# BUS.net
KiCad netlist of a schematic drawn in EAGLE
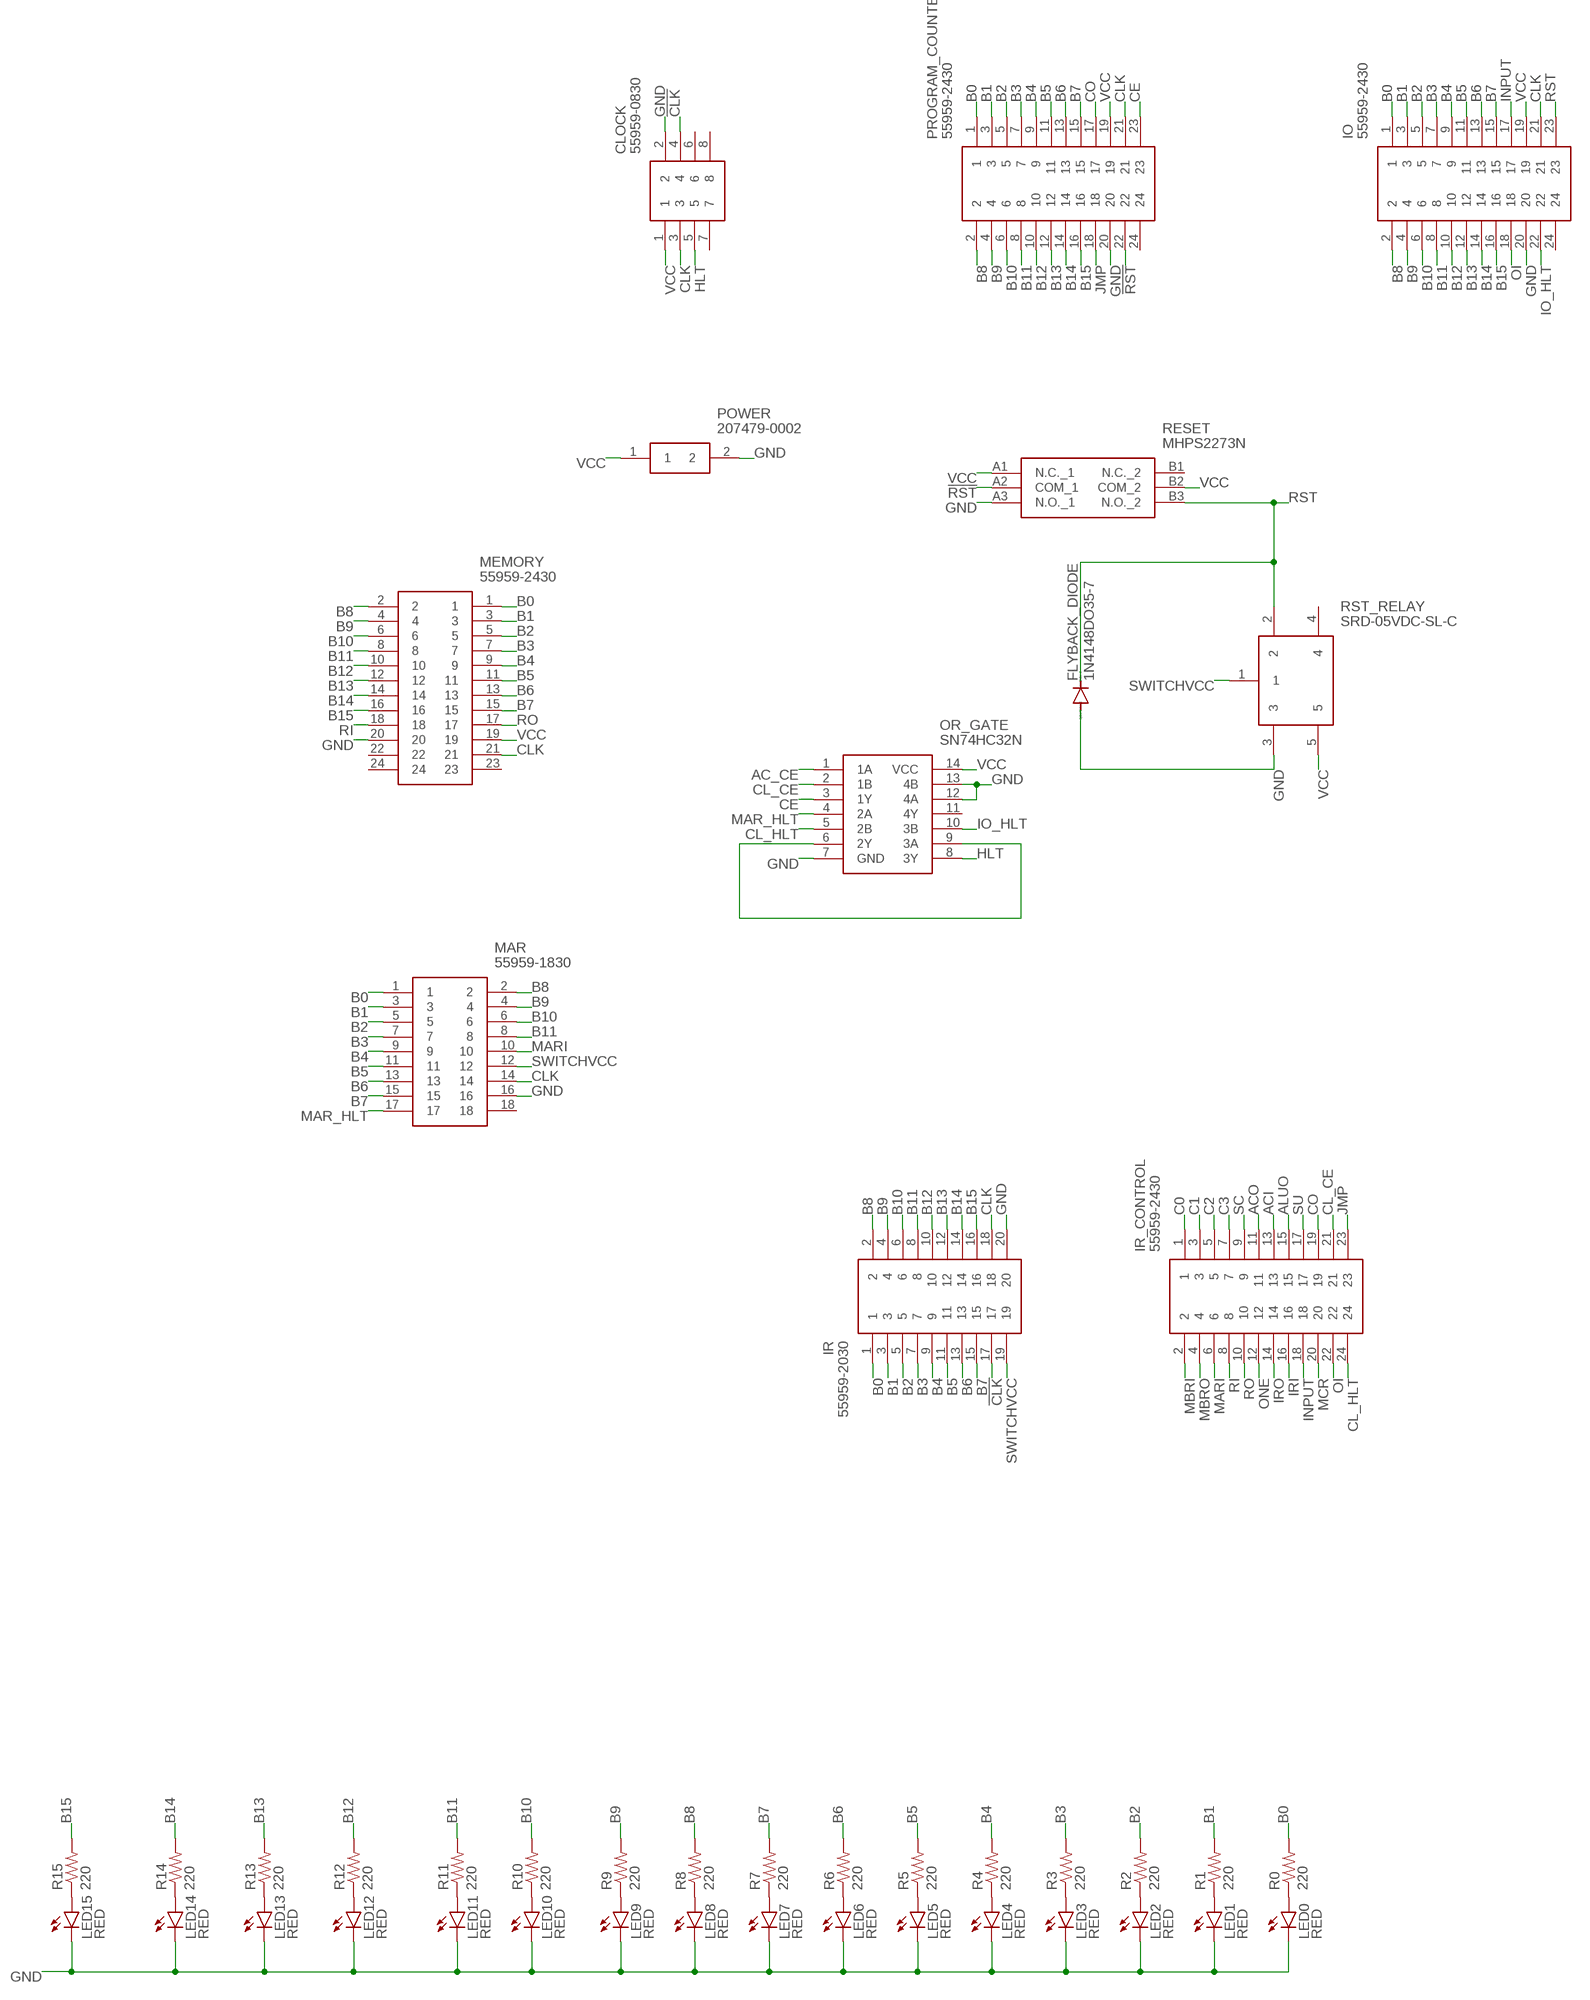
[diagram p0: schematic, sheet 1, part 1 of 2]
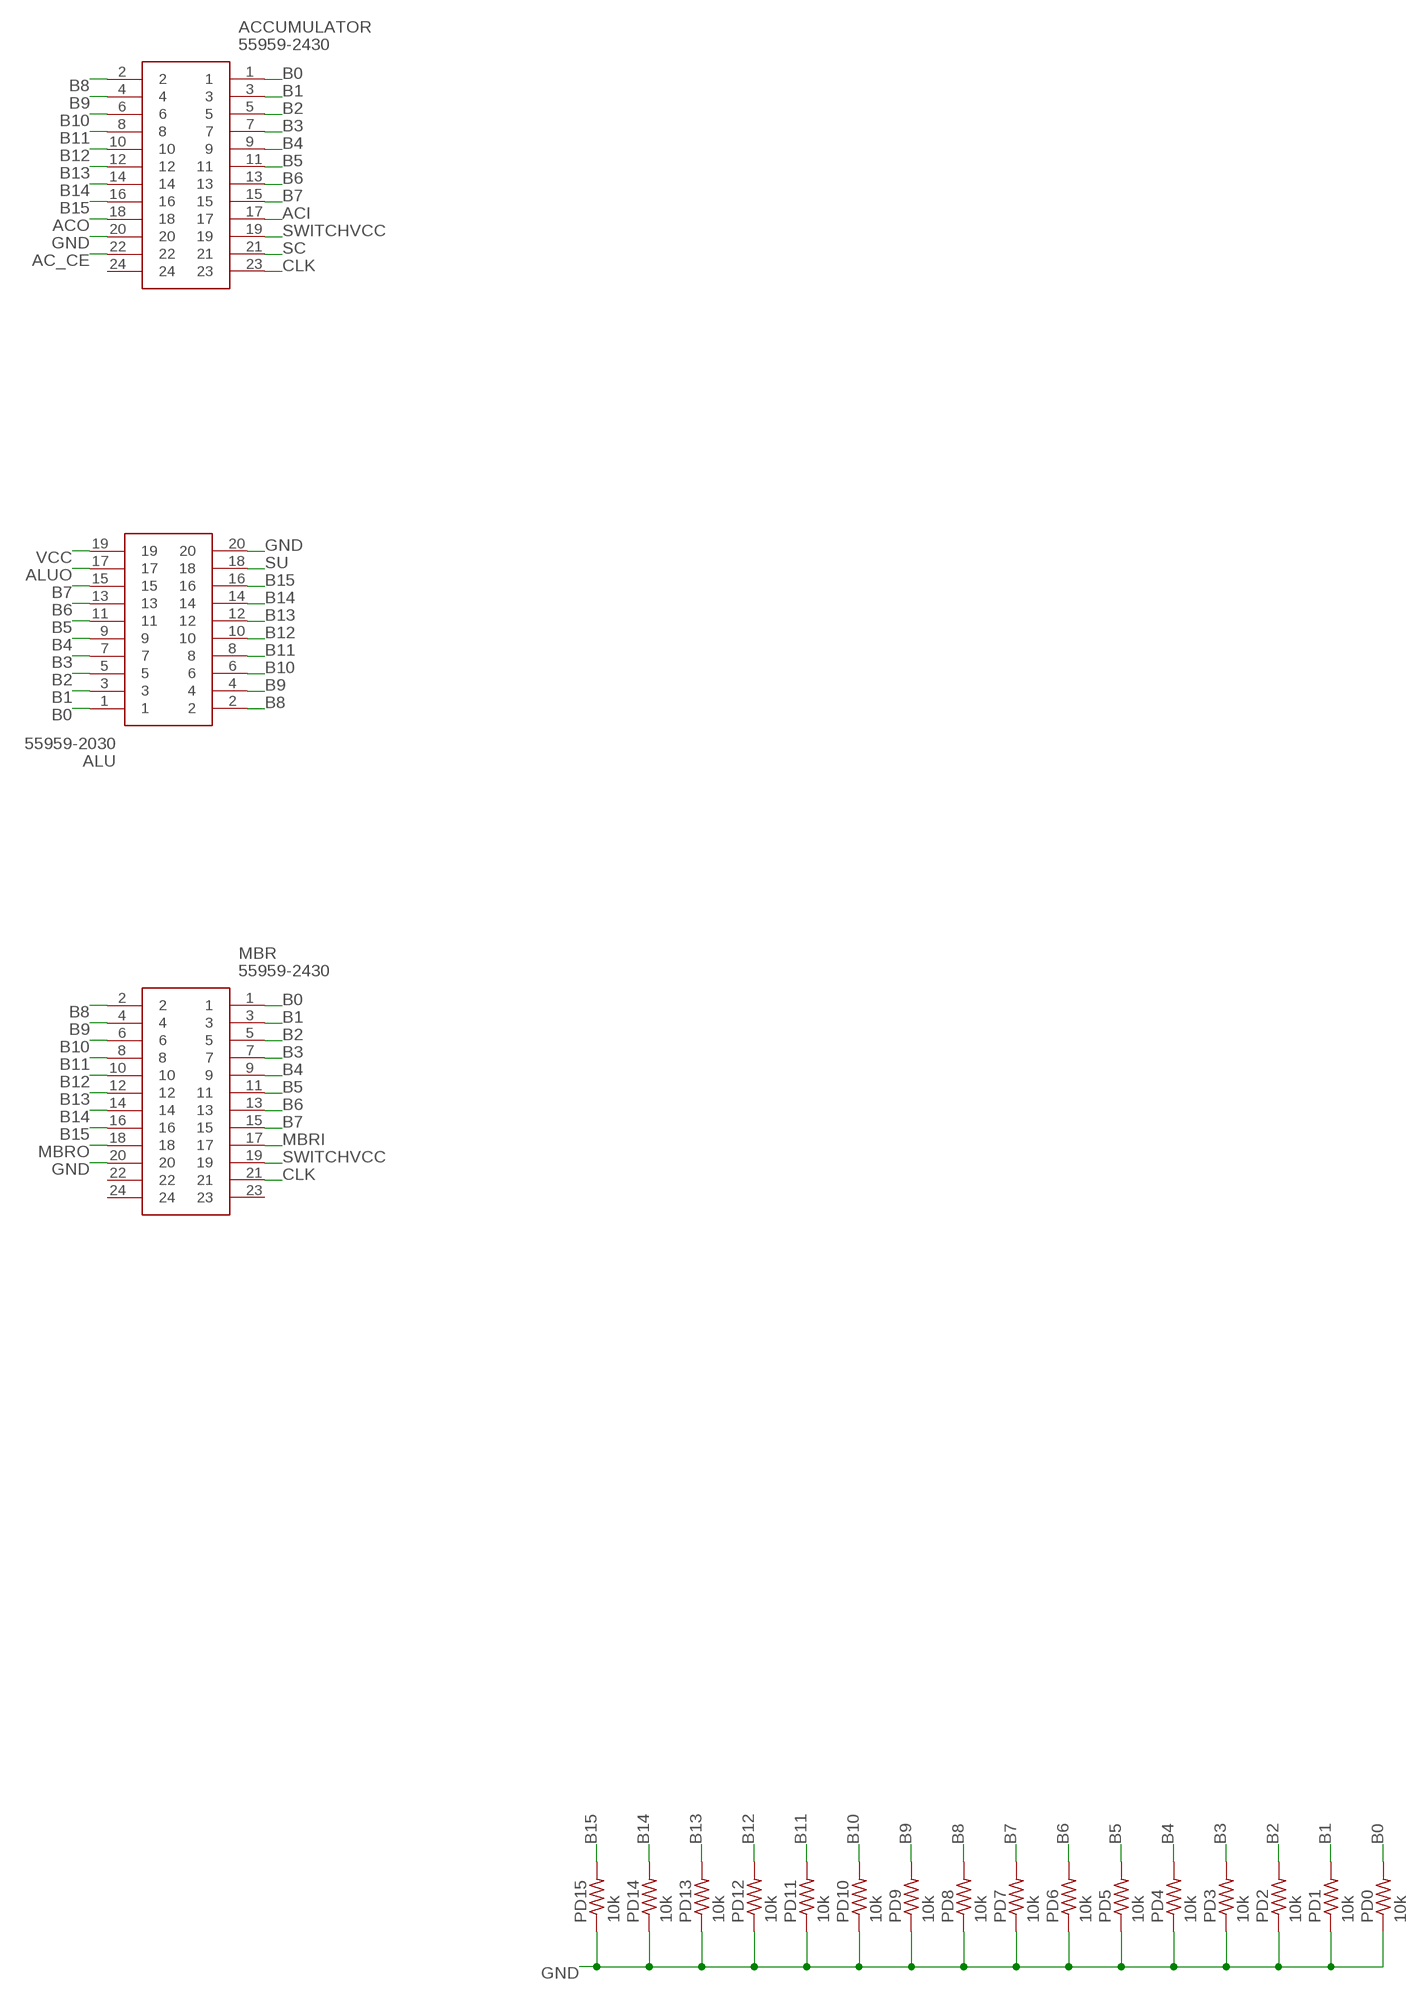
[diagram p1: schematic, sheet 1, part 2 of 2]

(export (version "E")
  (design (tool "Eeschema 10.0.6"))
  (components
    (comp (ref "ACCUMULATOR")
      (value "55959-2430")
      (footprint "eagle-import:559592430")
      (fields (field (name "MOUSER_PART_NUMBER") "538-55959-2430"))
      (libsource (lib "eagle-import") (part "55959-2430"))
    )
    (comp (ref "ALU")
      (value "55959-2030")
      (footprint "eagle-import:55959-2030_1")
      (fields (field (name "MOUSER_PART_NUMBER") "538-55959-2030"))
      (libsource (lib "eagle-import") (part "55959-2030"))
    )
    (comp (ref "CLOCK")
      (value "55959-0830")
      (footprint "eagle-import:SHDR8W65P250X200_2X4_1140X1400")
      (fields (field (name "MOUSER_PART_NUMBER") "538-55959-0830"))
      (libsource (lib "eagle-import") (part "55959-0830"))
    )
    (comp (ref "FLYBACK_DIODE")
      (value "1N4148DO35-7")
      (footprint "eagle-import:DO35-7")
      (libsource (lib "eagle-import") (part "1N4148DO35-7"))
    )
    (comp (ref "IO")
      (value "55959-2430")
      (footprint "eagle-import:559592430")
      (fields (field (name "MOUSER_PART_NUMBER") "538-55959-2430"))
      (libsource (lib "eagle-import") (part "55959-2430"))
    )
    (comp (ref "IR")
      (value "55959-2030")
      (footprint "eagle-import:55959-2030_1")
      (fields (field (name "MOUSER_PART_NUMBER") "538-55959-2030"))
      (libsource (lib "eagle-import") (part "55959-2030"))
    )
    (comp (ref "IR_CONTROL")
      (value "55959-2430")
      (footprint "eagle-import:559592430")
      (fields (field (name "MOUSER_PART_NUMBER") "538-55959-2430"))
      (libsource (lib "eagle-import") (part "55959-2430"))
    )
    (comp (ref "LED0")
      (value "RED")
      (footprint "eagle-import:LED3MM")
      (libsource (lib "eagle-import") (part "LED3MM"))
    )
    (comp (ref "LED1")
      (value "RED")
      (footprint "eagle-import:LED3MM")
      (libsource (lib "eagle-import") (part "LED3MM"))
    )
    (comp (ref "LED2")
      (value "RED")
      (footprint "eagle-import:LED3MM")
      (libsource (lib "eagle-import") (part "LED3MM"))
    )
    (comp (ref "LED3")
      (value "RED")
      (footprint "eagle-import:LED3MM")
      (libsource (lib "eagle-import") (part "LED3MM"))
    )
    (comp (ref "LED4")
      (value "RED")
      (footprint "eagle-import:LED3MM")
      (libsource (lib "eagle-import") (part "LED3MM"))
    )
    (comp (ref "LED5")
      (value "RED")
      (footprint "eagle-import:LED3MM")
      (libsource (lib "eagle-import") (part "LED3MM"))
    )
    (comp (ref "LED6")
      (value "RED")
      (footprint "eagle-import:LED3MM")
      (libsource (lib "eagle-import") (part "LED3MM"))
    )
    (comp (ref "LED7")
      (value "RED")
      (footprint "eagle-import:LED3MM")
      (libsource (lib "eagle-import") (part "LED3MM"))
    )
    (comp (ref "LED8")
      (value "RED")
      (footprint "eagle-import:LED3MM")
      (libsource (lib "eagle-import") (part "LED3MM"))
    )
    (comp (ref "LED9")
      (value "RED")
      (footprint "eagle-import:LED3MM")
      (libsource (lib "eagle-import") (part "LED3MM"))
    )
    (comp (ref "LED10")
      (value "RED")
      (footprint "eagle-import:LED3MM")
      (libsource (lib "eagle-import") (part "LED3MM"))
    )
    (comp (ref "LED11")
      (value "RED")
      (footprint "eagle-import:LED3MM")
      (libsource (lib "eagle-import") (part "LED3MM"))
    )
    (comp (ref "LED12")
      (value "RED")
      (footprint "eagle-import:LED3MM")
      (libsource (lib "eagle-import") (part "LED3MM"))
    )
    (comp (ref "LED13")
      (value "RED")
      (footprint "eagle-import:LED3MM")
      (libsource (lib "eagle-import") (part "LED3MM"))
    )
    (comp (ref "LED14")
      (value "RED")
      (footprint "eagle-import:LED3MM")
      (libsource (lib "eagle-import") (part "LED3MM"))
    )
    (comp (ref "LED15")
      (value "RED")
      (footprint "eagle-import:LED3MM")
      (libsource (lib "eagle-import") (part "LED3MM"))
    )
    (comp (ref "MAR")
      (value "55959-1830")
      (footprint "eagle-import:SHDR18W65P250X200_2X9_2140X140")
      (fields (field (name "MOUSER_PART_NUMBER") "538-55959-1830"))
      (libsource (lib "eagle-import") (part "55959-1830"))
    )
    (comp (ref "MBR")
      (value "55959-2430")
      (footprint "eagle-import:559592430")
      (fields (field (name "MOUSER_PART_NUMBER") "538-55959-2430"))
      (libsource (lib "eagle-import") (part "55959-2430"))
    )
    (comp (ref "MEMORY")
      (value "55959-2430")
      (footprint "eagle-import:559592430")
      (fields (field (name "MOUSER_PART_NUMBER") "538-55959-2430"))
      (libsource (lib "eagle-import") (part "55959-2430"))
    )
    (comp (ref "OR_GATE")
      (value "SN74HC32N")
      (footprint "eagle-import:DIP794W53P254L1930H508Q14N")
      (fields (field (name "MOUSER_PART_NUMBER") "595-SN74HC32N"))
      (libsource (lib "eagle-import") (part "SN74HC32N"))
    )
    (comp (ref "PD0")
      (value "10k")
      (footprint "eagle-import:0204_7")
      (libsource (lib "eagle-import") (part "R-US_0204/7"))
    )
    (comp (ref "PD1")
      (value "10k")
      (footprint "eagle-import:0204_7")
      (libsource (lib "eagle-import") (part "R-US_0204/7"))
    )
    (comp (ref "PD2")
      (value "10k")
      (footprint "eagle-import:0204_7")
      (libsource (lib "eagle-import") (part "R-US_0204/7"))
    )
    (comp (ref "PD3")
      (value "10k")
      (footprint "eagle-import:0204_7")
      (libsource (lib "eagle-import") (part "R-US_0204/7"))
    )
    (comp (ref "PD4")
      (value "10k")
      (footprint "eagle-import:0204_7")
      (libsource (lib "eagle-import") (part "R-US_0204/7"))
    )
    (comp (ref "PD5")
      (value "10k")
      (footprint "eagle-import:0204_7")
      (libsource (lib "eagle-import") (part "R-US_0204/7"))
    )
    (comp (ref "PD6")
      (value "10k")
      (footprint "eagle-import:0204_7")
      (libsource (lib "eagle-import") (part "R-US_0204/7"))
    )
    (comp (ref "PD7")
      (value "10k")
      (footprint "eagle-import:0204_7")
      (libsource (lib "eagle-import") (part "R-US_0204/7"))
    )
    (comp (ref "PD8")
      (value "10k")
      (footprint "eagle-import:0204_7")
      (libsource (lib "eagle-import") (part "R-US_0204/7"))
    )
    (comp (ref "PD9")
      (value "10k")
      (footprint "eagle-import:0204_7")
      (libsource (lib "eagle-import") (part "R-US_0204/7"))
    )
    (comp (ref "PD10")
      (value "10k")
      (footprint "eagle-import:0204_7")
      (libsource (lib "eagle-import") (part "R-US_0204/7"))
    )
    (comp (ref "PD11")
      (value "10k")
      (footprint "eagle-import:0204_7")
      (libsource (lib "eagle-import") (part "R-US_0204/7"))
    )
    (comp (ref "PD12")
      (value "10k")
      (footprint "eagle-import:0204_7")
      (libsource (lib "eagle-import") (part "R-US_0204/7"))
    )
    (comp (ref "PD13")
      (value "10k")
      (footprint "eagle-import:0204_7")
      (libsource (lib "eagle-import") (part "R-US_0204/7"))
    )
    (comp (ref "PD14")
      (value "10k")
      (footprint "eagle-import:0204_7")
      (libsource (lib "eagle-import") (part "R-US_0204/7"))
    )
    (comp (ref "PD15")
      (value "10k")
      (footprint "eagle-import:0204_7")
      (libsource (lib "eagle-import") (part "R-US_0204/7"))
    )
    (comp (ref "POWER")
      (value "207479-0002")
      (footprint "eagle-import:2074790002")
      (fields (field (name "MOUSER_PART_NUMBER") "538-207479-0002"))
      (libsource (lib "eagle-import") (part "207479-0002"))
    )
    (comp (ref "PROGRAM_COUNTER")
      (value "55959-2430")
      (footprint "eagle-import:559592430")
      (fields (field (name "MOUSER_PART_NUMBER") "538-55959-2430"))
      (libsource (lib "eagle-import") (part "55959-2430"))
    )
    (comp (ref "R0")
      (value "220")
      (footprint "eagle-import:0204_7")
      (libsource (lib "eagle-import") (part "R-US_0204/7"))
    )
    (comp (ref "R1")
      (value "220")
      (footprint "eagle-import:0204_7")
      (libsource (lib "eagle-import") (part "R-US_0204/7"))
    )
    (comp (ref "R2")
      (value "220")
      (footprint "eagle-import:0204_7")
      (libsource (lib "eagle-import") (part "R-US_0204/7"))
    )
    (comp (ref "R3")
      (value "220")
      (footprint "eagle-import:0204_7")
      (libsource (lib "eagle-import") (part "R-US_0204/7"))
    )
    (comp (ref "R4")
      (value "220")
      (footprint "eagle-import:0204_7")
      (libsource (lib "eagle-import") (part "R-US_0204/7"))
    )
    (comp (ref "R5")
      (value "220")
      (footprint "eagle-import:0204_7")
      (libsource (lib "eagle-import") (part "R-US_0204/7"))
    )
    (comp (ref "R6")
      (value "220")
      (footprint "eagle-import:0204_7")
      (libsource (lib "eagle-import") (part "R-US_0204/7"))
    )
    (comp (ref "R7")
      (value "220")
      (footprint "eagle-import:0204_7")
      (libsource (lib "eagle-import") (part "R-US_0204/7"))
    )
    (comp (ref "R8")
      (value "220")
      (footprint "eagle-import:0204_7")
      (libsource (lib "eagle-import") (part "R-US_0204/7"))
    )
    (comp (ref "R9")
      (value "220")
      (footprint "eagle-import:0204_7")
      (libsource (lib "eagle-import") (part "R-US_0204/7"))
    )
    (comp (ref "R10")
      (value "220")
      (footprint "eagle-import:0204_7")
      (libsource (lib "eagle-import") (part "R-US_0204/7"))
    )
    (comp (ref "R11")
      (value "220")
      (footprint "eagle-import:0204_7")
      (libsource (lib "eagle-import") (part "R-US_0204/7"))
    )
    (comp (ref "R12")
      (value "220")
      (footprint "eagle-import:0204_7")
      (libsource (lib "eagle-import") (part "R-US_0204/7"))
    )
    (comp (ref "R13")
      (value "220")
      (footprint "eagle-import:0204_7")
      (libsource (lib "eagle-import") (part "R-US_0204/7"))
    )
    (comp (ref "R14")
      (value "220")
      (footprint "eagle-import:0204_7")
      (libsource (lib "eagle-import") (part "R-US_0204/7"))
    )
    (comp (ref "R15")
      (value "220")
      (footprint "eagle-import:0204_7")
      (libsource (lib "eagle-import") (part "R-US_0204/7"))
    )
    (comp (ref "RESET")
      (value "MHPS2273N")
      (footprint "eagle-import:MHPS2273N")
      (fields (field (name "MOUSER_PART_NUMBER") "642-MHPS2273N"))
      (libsource (lib "eagle-import") (part "MHPS2273N"))
    )
    (comp (ref "RST_RELAY")
      (value "SRD-05VDC-SL-C")
      (footprint "eagle-import:SRD")
      (libsource (lib "eagle-import") (part "SRD-05VDC-SL-C"))
    )
  )
  (nets
    (net (code "1") (name "/ACI") (class "Default")
      (node (ref "ACCUMULATOR") (pin "17") (pinfunction "17_17") (pintype "bidirectional"))
      (node (ref "IR_CONTROL") (pin "13") (pinfunction "13_13") (pintype "bidirectional"))
    )
    (net (code "2") (name "/ACO") (class "Default")
      (node (ref "ACCUMULATOR") (pin "18") (pinfunction "18_18") (pintype "bidirectional"))
      (node (ref "IR_CONTROL") (pin "11") (pinfunction "11_11") (pintype "bidirectional"))
    )
    (net (code "3") (name "/AC_CE") (class "Default")
      (node (ref "ACCUMULATOR") (pin "22") (pinfunction "22_22") (pintype "bidirectional"))
      (node (ref "OR_GATE") (pin "1") (pinfunction "1A_1") (pintype "bidirectional"))
    )
    (net (code "4") (name "/ALUO") (class "Default")
      (node (ref "ALU") (pin "17") (pinfunction "17_17") (pintype "bidirectional"))
      (node (ref "IR_CONTROL") (pin "15") (pinfunction "15_15") (pintype "bidirectional"))
    )
    (net (code "5") (name "/B0") (class "Default")
      (node (ref "ACCUMULATOR") (pin "1") (pinfunction "1_1") (pintype "bidirectional"))
      (node (ref "ALU") (pin "1") (pinfunction "1_1") (pintype "bidirectional"))
      (node (ref "IO") (pin "1") (pinfunction "1_1") (pintype "bidirectional"))
      (node (ref "IR") (pin "1") (pinfunction "1_1") (pintype "bidirectional"))
      (node (ref "MAR") (pin "1") (pinfunction "1_1") (pintype "bidirectional"))
      (node (ref "MBR") (pin "1") (pinfunction "1_1") (pintype "bidirectional"))
      (node (ref "MEMORY") (pin "1") (pinfunction "1_1") (pintype "bidirectional"))
      (node (ref "PD0") (pin "2") (pinfunction "2_2") (pintype "passive"))
      (node (ref "PROGRAM_COUNTER") (pin "1") (pinfunction "1_1") (pintype "bidirectional"))
      (node (ref "R0") (pin "2") (pinfunction "2_2") (pintype "passive"))
    )
    (net (code "6") (name "/B1") (class "Default")
      (node (ref "ACCUMULATOR") (pin "3") (pinfunction "3_3") (pintype "bidirectional"))
      (node (ref "ALU") (pin "3") (pinfunction "3_3") (pintype "bidirectional"))
      (node (ref "IO") (pin "3") (pinfunction "3_3") (pintype "bidirectional"))
      (node (ref "IR") (pin "3") (pinfunction "3_3") (pintype "bidirectional"))
      (node (ref "MAR") (pin "3") (pinfunction "3_3") (pintype "bidirectional"))
      (node (ref "MBR") (pin "3") (pinfunction "3_3") (pintype "bidirectional"))
      (node (ref "MEMORY") (pin "3") (pinfunction "3_3") (pintype "bidirectional"))
      (node (ref "PD1") (pin "2") (pinfunction "2_2") (pintype "passive"))
      (node (ref "PROGRAM_COUNTER") (pin "3") (pinfunction "3_3") (pintype "bidirectional"))
      (node (ref "R1") (pin "2") (pinfunction "2_2") (pintype "passive"))
    )
    (net (code "7") (name "/B2") (class "Default")
      (node (ref "ACCUMULATOR") (pin "5") (pinfunction "5_5") (pintype "bidirectional"))
      (node (ref "ALU") (pin "5") (pinfunction "5_5") (pintype "bidirectional"))
      (node (ref "IO") (pin "5") (pinfunction "5_5") (pintype "bidirectional"))
      (node (ref "IR") (pin "5") (pinfunction "5_5") (pintype "bidirectional"))
      (node (ref "MAR") (pin "5") (pinfunction "5_5") (pintype "bidirectional"))
      (node (ref "MBR") (pin "5") (pinfunction "5_5") (pintype "bidirectional"))
      (node (ref "MEMORY") (pin "5") (pinfunction "5_5") (pintype "bidirectional"))
      (node (ref "PD2") (pin "2") (pinfunction "2_2") (pintype "passive"))
      (node (ref "PROGRAM_COUNTER") (pin "5") (pinfunction "5_5") (pintype "bidirectional"))
      (node (ref "R2") (pin "2") (pinfunction "2_2") (pintype "passive"))
    )
    (net (code "8") (name "/B3") (class "Default")
      (node (ref "ACCUMULATOR") (pin "7") (pinfunction "7_7") (pintype "bidirectional"))
      (node (ref "ALU") (pin "7") (pinfunction "7_7") (pintype "bidirectional"))
      (node (ref "IO") (pin "7") (pinfunction "7_7") (pintype "bidirectional"))
      (node (ref "IR") (pin "7") (pinfunction "7_7") (pintype "bidirectional"))
      (node (ref "MAR") (pin "7") (pinfunction "7_7") (pintype "bidirectional"))
      (node (ref "MBR") (pin "7") (pinfunction "7_7") (pintype "bidirectional"))
      (node (ref "MEMORY") (pin "7") (pinfunction "7_7") (pintype "bidirectional"))
      (node (ref "PD3") (pin "2") (pinfunction "2_2") (pintype "passive"))
      (node (ref "PROGRAM_COUNTER") (pin "7") (pinfunction "7_7") (pintype "bidirectional"))
      (node (ref "R3") (pin "2") (pinfunction "2_2") (pintype "passive"))
    )
    (net (code "9") (name "/B4") (class "Default")
      (node (ref "ACCUMULATOR") (pin "9") (pinfunction "9_9") (pintype "bidirectional"))
      (node (ref "ALU") (pin "9") (pinfunction "9_9") (pintype "bidirectional"))
      (node (ref "IO") (pin "9") (pinfunction "9_9") (pintype "bidirectional"))
      (node (ref "IR") (pin "9") (pinfunction "9_9") (pintype "bidirectional"))
      (node (ref "MAR") (pin "9") (pinfunction "9_9") (pintype "bidirectional"))
      (node (ref "MBR") (pin "9") (pinfunction "9_9") (pintype "bidirectional"))
      (node (ref "MEMORY") (pin "9") (pinfunction "9_9") (pintype "bidirectional"))
      (node (ref "PD4") (pin "2") (pinfunction "2_2") (pintype "passive"))
      (node (ref "PROGRAM_COUNTER") (pin "9") (pinfunction "9_9") (pintype "bidirectional"))
      (node (ref "R4") (pin "2") (pinfunction "2_2") (pintype "passive"))
    )
    (net (code "10") (name "/B5") (class "Default")
      (node (ref "ACCUMULATOR") (pin "11") (pinfunction "11_11") (pintype "bidirectional"))
      (node (ref "ALU") (pin "11") (pinfunction "11_11") (pintype "bidirectional"))
      (node (ref "IO") (pin "11") (pinfunction "11_11") (pintype "bidirectional"))
      (node (ref "IR") (pin "11") (pinfunction "11_11") (pintype "bidirectional"))
      (node (ref "MAR") (pin "11") (pinfunction "11_11") (pintype "bidirectional"))
      (node (ref "MBR") (pin "11") (pinfunction "11_11") (pintype "bidirectional"))
      (node (ref "MEMORY") (pin "11") (pinfunction "11_11") (pintype "bidirectional"))
      (node (ref "PD5") (pin "2") (pinfunction "2_2") (pintype "passive"))
      (node (ref "PROGRAM_COUNTER") (pin "11") (pinfunction "11_11") (pintype "bidirectional"))
      (node (ref "R5") (pin "2") (pinfunction "2_2") (pintype "passive"))
    )
    (net (code "11") (name "/B6") (class "Default")
      (node (ref "ACCUMULATOR") (pin "13") (pinfunction "13_13") (pintype "bidirectional"))
      (node (ref "ALU") (pin "13") (pinfunction "13_13") (pintype "bidirectional"))
      (node (ref "IO") (pin "13") (pinfunction "13_13") (pintype "bidirectional"))
      (node (ref "IR") (pin "13") (pinfunction "13_13") (pintype "bidirectional"))
      (node (ref "MAR") (pin "13") (pinfunction "13_13") (pintype "bidirectional"))
      (node (ref "MBR") (pin "13") (pinfunction "13_13") (pintype "bidirectional"))
      (node (ref "MEMORY") (pin "13") (pinfunction "13_13") (pintype "bidirectional"))
      (node (ref "PD6") (pin "2") (pinfunction "2_2") (pintype "passive"))
      (node (ref "PROGRAM_COUNTER") (pin "13") (pinfunction "13_13") (pintype "bidirectional"))
      (node (ref "R6") (pin "2") (pinfunction "2_2") (pintype "passive"))
    )
    (net (code "12") (name "/B7") (class "Default")
      (node (ref "ACCUMULATOR") (pin "15") (pinfunction "15_15") (pintype "bidirectional"))
      (node (ref "ALU") (pin "15") (pinfunction "15_15") (pintype "bidirectional"))
      (node (ref "IO") (pin "15") (pinfunction "15_15") (pintype "bidirectional"))
      (node (ref "IR") (pin "15") (pinfunction "15_15") (pintype "bidirectional"))
      (node (ref "MAR") (pin "15") (pinfunction "15_15") (pintype "bidirectional"))
      (node (ref "MBR") (pin "15") (pinfunction "15_15") (pintype "bidirectional"))
      (node (ref "MEMORY") (pin "15") (pinfunction "15_15") (pintype "bidirectional"))
      (node (ref "PD7") (pin "2") (pinfunction "2_2") (pintype "passive"))
      (node (ref "PROGRAM_COUNTER") (pin "15") (pinfunction "15_15") (pintype "bidirectional"))
      (node (ref "R7") (pin "2") (pinfunction "2_2") (pintype "passive"))
    )
    (net (code "13") (name "/B8") (class "Default")
      (node (ref "ACCUMULATOR") (pin "2") (pinfunction "2_2") (pintype "bidirectional"))
      (node (ref "ALU") (pin "2") (pinfunction "2_2") (pintype "bidirectional"))
      (node (ref "IO") (pin "2") (pinfunction "2_2") (pintype "bidirectional"))
      (node (ref "IR") (pin "2") (pinfunction "2_2") (pintype "bidirectional"))
      (node (ref "MAR") (pin "2") (pinfunction "2_2") (pintype "bidirectional"))
      (node (ref "MBR") (pin "2") (pinfunction "2_2") (pintype "bidirectional"))
      (node (ref "MEMORY") (pin "2") (pinfunction "2_2") (pintype "bidirectional"))
      (node (ref "PD8") (pin "2") (pinfunction "2_2") (pintype "passive"))
      (node (ref "PROGRAM_COUNTER") (pin "2") (pinfunction "2_2") (pintype "bidirectional"))
      (node (ref "R8") (pin "2") (pinfunction "2_2") (pintype "passive"))
    )
    (net (code "14") (name "/B9") (class "Default")
      (node (ref "ACCUMULATOR") (pin "4") (pinfunction "4_4") (pintype "bidirectional"))
      (node (ref "ALU") (pin "4") (pinfunction "4_4") (pintype "bidirectional"))
      (node (ref "IO") (pin "4") (pinfunction "4_4") (pintype "bidirectional"))
      (node (ref "IR") (pin "4") (pinfunction "4_4") (pintype "bidirectional"))
      (node (ref "MAR") (pin "4") (pinfunction "4_4") (pintype "bidirectional"))
      (node (ref "MBR") (pin "4") (pinfunction "4_4") (pintype "bidirectional"))
      (node (ref "MEMORY") (pin "4") (pinfunction "4_4") (pintype "bidirectional"))
      (node (ref "PD9") (pin "2") (pinfunction "2_2") (pintype "passive"))
      (node (ref "PROGRAM_COUNTER") (pin "4") (pinfunction "4_4") (pintype "bidirectional"))
      (node (ref "R9") (pin "2") (pinfunction "2_2") (pintype "passive"))
    )
    (net (code "15") (name "/B10") (class "Default")
      (node (ref "ACCUMULATOR") (pin "6") (pinfunction "6_6") (pintype "bidirectional"))
      (node (ref "ALU") (pin "6") (pinfunction "6_6") (pintype "bidirectional"))
      (node (ref "IO") (pin "6") (pinfunction "6_6") (pintype "bidirectional"))
      (node (ref "IR") (pin "6") (pinfunction "6_6") (pintype "bidirectional"))
      (node (ref "MAR") (pin "6") (pinfunction "6_6") (pintype "bidirectional"))
      (node (ref "MBR") (pin "6") (pinfunction "6_6") (pintype "bidirectional"))
      (node (ref "MEMORY") (pin "6") (pinfunction "6_6") (pintype "bidirectional"))
      (node (ref "PD10") (pin "2") (pinfunction "2_2") (pintype "passive"))
      (node (ref "PROGRAM_COUNTER") (pin "6") (pinfunction "6_6") (pintype "bidirectional"))
      (node (ref "R10") (pin "2") (pinfunction "2_2") (pintype "passive"))
    )
    (net (code "16") (name "/B11") (class "Default")
      (node (ref "ACCUMULATOR") (pin "8") (pinfunction "8_8") (pintype "bidirectional"))
      (node (ref "ALU") (pin "8") (pinfunction "8_8") (pintype "bidirectional"))
      (node (ref "IO") (pin "8") (pinfunction "8_8") (pintype "bidirectional"))
      (node (ref "IR") (pin "8") (pinfunction "8_8") (pintype "bidirectional"))
      (node (ref "MAR") (pin "8") (pinfunction "8_8") (pintype "bidirectional"))
      (node (ref "MBR") (pin "8") (pinfunction "8_8") (pintype "bidirectional"))
      (node (ref "MEMORY") (pin "8") (pinfunction "8_8") (pintype "bidirectional"))
      (node (ref "PD11") (pin "2") (pinfunction "2_2") (pintype "passive"))
      (node (ref "PROGRAM_COUNTER") (pin "8") (pinfunction "8_8") (pintype "bidirectional"))
      (node (ref "R11") (pin "2") (pinfunction "2_2") (pintype "passive"))
    )
    (net (code "17") (name "/B12") (class "Default")
      (node (ref "ACCUMULATOR") (pin "10") (pinfunction "10_10") (pintype "bidirectional"))
      (node (ref "ALU") (pin "10") (pinfunction "10_10") (pintype "bidirectional"))
      (node (ref "IO") (pin "10") (pinfunction "10_10") (pintype "bidirectional"))
      (node (ref "IR") (pin "10") (pinfunction "10_10") (pintype "bidirectional"))
      (node (ref "MBR") (pin "10") (pinfunction "10_10") (pintype "bidirectional"))
      (node (ref "MEMORY") (pin "10") (pinfunction "10_10") (pintype "bidirectional"))
      (node (ref "PD12") (pin "2") (pinfunction "2_2") (pintype "passive"))
      (node (ref "PROGRAM_COUNTER") (pin "10") (pinfunction "10_10") (pintype "bidirectional"))
      (node (ref "R12") (pin "2") (pinfunction "2_2") (pintype "passive"))
    )
    (net (code "18") (name "/B13") (class "Default")
      (node (ref "ACCUMULATOR") (pin "12") (pinfunction "12_12") (pintype "bidirectional"))
      (node (ref "ALU") (pin "12") (pinfunction "12_12") (pintype "bidirectional"))
      (node (ref "IO") (pin "12") (pinfunction "12_12") (pintype "bidirectional"))
      (node (ref "IR") (pin "12") (pinfunction "12_12") (pintype "bidirectional"))
      (node (ref "MBR") (pin "12") (pinfunction "12_12") (pintype "bidirectional"))
      (node (ref "MEMORY") (pin "12") (pinfunction "12_12") (pintype "bidirectional"))
      (node (ref "PD13") (pin "2") (pinfunction "2_2") (pintype "passive"))
      (node (ref "PROGRAM_COUNTER") (pin "12") (pinfunction "12_12") (pintype "bidirectional"))
      (node (ref "R13") (pin "2") (pinfunction "2_2") (pintype "passive"))
    )
    (net (code "19") (name "/B14") (class "Default")
      (node (ref "ACCUMULATOR") (pin "14") (pinfunction "14_14") (pintype "bidirectional"))
      (node (ref "ALU") (pin "14") (pinfunction "14_14") (pintype "bidirectional"))
      (node (ref "IO") (pin "14") (pinfunction "14_14") (pintype "bidirectional"))
      (node (ref "IR") (pin "14") (pinfunction "14_14") (pintype "bidirectional"))
      (node (ref "MBR") (pin "14") (pinfunction "14_14") (pintype "bidirectional"))
      (node (ref "MEMORY") (pin "14") (pinfunction "14_14") (pintype "bidirectional"))
      (node (ref "PD14") (pin "2") (pinfunction "2_2") (pintype "passive"))
      (node (ref "PROGRAM_COUNTER") (pin "14") (pinfunction "14_14") (pintype "bidirectional"))
      (node (ref "R14") (pin "2") (pinfunction "2_2") (pintype "passive"))
    )
    (net (code "20") (name "/B15") (class "Default")
      (node (ref "ACCUMULATOR") (pin "16") (pinfunction "16_16") (pintype "bidirectional"))
      (node (ref "ALU") (pin "16") (pinfunction "16_16") (pintype "bidirectional"))
      (node (ref "IO") (pin "16") (pinfunction "16_16") (pintype "bidirectional"))
      (node (ref "IR") (pin "16") (pinfunction "16_16") (pintype "bidirectional"))
      (node (ref "MBR") (pin "16") (pinfunction "16_16") (pintype "bidirectional"))
      (node (ref "MEMORY") (pin "16") (pinfunction "16_16") (pintype "bidirectional"))
      (node (ref "PD15") (pin "2") (pinfunction "2_2") (pintype "passive"))
      (node (ref "PROGRAM_COUNTER") (pin "16") (pinfunction "16_16") (pintype "bidirectional"))
      (node (ref "R15") (pin "2") (pinfunction "2_2") (pintype "passive"))
    )
    (net (code "21") (name "/C0") (class "Default")
      (node (ref "IR_CONTROL") (pin "1") (pinfunction "1_1") (pintype "bidirectional"))
    )
    (net (code "22") (name "/C1") (class "Default")
      (node (ref "IR_CONTROL") (pin "3") (pinfunction "3_3") (pintype "bidirectional"))
    )
    (net (code "23") (name "/C2") (class "Default")
      (node (ref "IR_CONTROL") (pin "5") (pinfunction "5_5") (pintype "bidirectional"))
    )
    (net (code "24") (name "/C3") (class "Default")
      (node (ref "IR_CONTROL") (pin "7") (pinfunction "7_7") (pintype "bidirectional"))
    )
    (net (code "25") (name "/CE") (class "Default")
      (node (ref "OR_GATE") (pin "3") (pinfunction "1Y_3") (pintype "bidirectional"))
      (node (ref "PROGRAM_COUNTER") (pin "23") (pinfunction "23_23") (pintype "bidirectional"))
    )
    (net (code "26") (name "/CLK") (class "Default")
      (node (ref "ACCUMULATOR") (pin "23") (pinfunction "23_23") (pintype "bidirectional"))
      (node (ref "CLOCK") (pin "3") (pinfunction "3_3") (pintype "bidirectional"))
      (node (ref "IO") (pin "21") (pinfunction "21_21") (pintype "bidirectional"))
      (node (ref "IR") (pin "18") (pinfunction "18_18") (pintype "bidirectional"))
      (node (ref "MAR") (pin "14") (pinfunction "14_14") (pintype "bidirectional"))
      (node (ref "MBR") (pin "21") (pinfunction "21_21") (pintype "bidirectional"))
      (node (ref "MEMORY") (pin "21") (pinfunction "21_21") (pintype "bidirectional"))
      (node (ref "PROGRAM_COUNTER") (pin "21") (pinfunction "21_21") (pintype "bidirectional"))
    )
    (net (code "27") (name "/CL_CE") (class "Default")
      (node (ref "IR_CONTROL") (pin "21") (pinfunction "21_21") (pintype "bidirectional"))
      (node (ref "OR_GATE") (pin "2") (pinfunction "1B_2") (pintype "bidirectional"))
    )
    (net (code "28") (name "/CL_HLT") (class "Default")
      (node (ref "IR_CONTROL") (pin "24") (pinfunction "24_24") (pintype "bidirectional"))
      (node (ref "OR_GATE") (pin "5") (pinfunction "2B_5") (pintype "bidirectional"))
    )
    (net (code "29") (name "/CO") (class "Default")
      (node (ref "IR_CONTROL") (pin "19") (pinfunction "19_19") (pintype "bidirectional"))
      (node (ref "PROGRAM_COUNTER") (pin "17") (pinfunction "17_17") (pintype "bidirectional"))
    )
    (net (code "30") (name "/GND") (class "Default")
      (node (ref "ACCUMULATOR") (pin "20") (pinfunction "20_20") (pintype "bidirectional"))
      (node (ref "ALU") (pin "20") (pinfunction "20_20") (pintype "bidirectional"))
      (node (ref "CLOCK") (pin "2") (pinfunction "2_2") (pintype "bidirectional"))
      (node (ref "FLYBACK_DIODE") (pin "A") (pinfunction "A_A") (pintype "passive"))
      (node (ref "IO") (pin "20") (pinfunction "20_20") (pintype "bidirectional"))
      (node (ref "IR") (pin "20") (pinfunction "20_20") (pintype "bidirectional"))
      (node (ref "LED0") (pin "K") (pinfunction "C_K") (pintype "passive"))
      (node (ref "LED1") (pin "K") (pinfunction "C_K") (pintype "passive"))
      (node (ref "LED10") (pin "K") (pinfunction "C_K") (pintype "passive"))
      (node (ref "LED11") (pin "K") (pinfunction "C_K") (pintype "passive"))
      (node (ref "LED12") (pin "K") (pinfunction "C_K") (pintype "passive"))
      (node (ref "LED13") (pin "K") (pinfunction "C_K") (pintype "passive"))
      (node (ref "LED14") (pin "K") (pinfunction "C_K") (pintype "passive"))
      (node (ref "LED15") (pin "K") (pinfunction "C_K") (pintype "passive"))
      (node (ref "LED2") (pin "K") (pinfunction "C_K") (pintype "passive"))
      (node (ref "LED3") (pin "K") (pinfunction "C_K") (pintype "passive"))
      (node (ref "LED4") (pin "K") (pinfunction "C_K") (pintype "passive"))
      (node (ref "LED5") (pin "K") (pinfunction "C_K") (pintype "passive"))
      (node (ref "LED6") (pin "K") (pinfunction "C_K") (pintype "passive"))
      (node (ref "LED7") (pin "K") (pinfunction "C_K") (pintype "passive"))
      (node (ref "LED8") (pin "K") (pinfunction "C_K") (pintype "passive"))
      (node (ref "LED9") (pin "K") (pinfunction "C_K") (pintype "passive"))
      (node (ref "MAR") (pin "16") (pinfunction "16_16") (pintype "bidirectional"))
      (node (ref "MBR") (pin "20") (pinfunction "20_20") (pintype "bidirectional"))
      (node (ref "MEMORY") (pin "20") (pinfunction "20_20") (pintype "bidirectional"))
      (node (ref "OR_GATE") (pin "12") (pinfunction "4A_12") (pintype "bidirectional"))
      (node (ref "OR_GATE") (pin "13") (pinfunction "4B_13") (pintype "bidirectional"))
      (node (ref "OR_GATE") (pin "7") (pinfunction "GND_7") (pintype "bidirectional"))
      (node (ref "PD0") (pin "1") (pinfunction "1_1") (pintype "passive"))
      (node (ref "PD1") (pin "1") (pinfunction "1_1") (pintype "passive"))
      (node (ref "PD10") (pin "1") (pinfunction "1_1") (pintype "passive"))
      (node (ref "PD11") (pin "1") (pinfunction "1_1") (pintype "passive"))
      (node (ref "PD12") (pin "1") (pinfunction "1_1") (pintype "passive"))
      (node (ref "PD13") (pin "1") (pinfunction "1_1") (pintype "passive"))
      (node (ref "PD14") (pin "1") (pinfunction "1_1") (pintype "passive"))
      (node (ref "PD15") (pin "1") (pinfunction "1_1") (pintype "passive"))
      (node (ref "PD2") (pin "1") (pinfunction "1_1") (pintype "passive"))
      (node (ref "PD3") (pin "1") (pinfunction "1_1") (pintype "passive"))
      (node (ref "PD4") (pin "1") (pinfunction "1_1") (pintype "passive"))
      (node (ref "PD5") (pin "1") (pinfunction "1_1") (pintype "passive"))
      (node (ref "PD6") (pin "1") (pinfunction "1_1") (pintype "passive"))
      (node (ref "PD7") (pin "1") (pinfunction "1_1") (pintype "passive"))
      (node (ref "PD8") (pin "1") (pinfunction "1_1") (pintype "passive"))
      (node (ref "PD9") (pin "1") (pinfunction "1_1") (pintype "passive"))
      (node (ref "POWER") (pin "2") (pinfunction "2_2") (pintype "bidirectional"))
      (node (ref "PROGRAM_COUNTER") (pin "20") (pinfunction "20_20") (pintype "bidirectional"))
      (node (ref "RESET") (pin "A3") (pinfunction "N.O._1_A3") (pintype "bidirectional"))
      (node (ref "RST_RELAY") (pin "3") (pinfunction "3_3") (pintype "bidirectional"))
    )
    (net (code "31") (name "/HLT") (class "Default")
      (node (ref "CLOCK") (pin "5") (pinfunction "5_5") (pintype "bidirectional"))
      (node (ref "OR_GATE") (pin "8") (pinfunction "3Y_8") (pintype "bidirectional"))
    )
    (net (code "32") (name "/INPUT") (class "Default")
      (node (ref "IO") (pin "17") (pinfunction "17_17") (pintype "bidirectional"))
      (node (ref "IR_CONTROL") (pin "18") (pinfunction "18_18") (pintype "bidirectional"))
    )
    (net (code "33") (name "/IO_HLT") (class "Default")
      (node (ref "IO") (pin "22") (pinfunction "22_22") (pintype "bidirectional"))
      (node (ref "OR_GATE") (pin "10") (pinfunction "3B_10") (pintype "bidirectional"))
    )
    (net (code "34") (name "/IRI") (class "Default")
      (node (ref "IR_CONTROL") (pin "16") (pinfunction "16_16") (pintype "bidirectional"))
    )
    (net (code "35") (name "/IRO") (class "Default")
      (node (ref "IR_CONTROL") (pin "14") (pinfunction "14_14") (pintype "bidirectional"))
    )
    (net (code "36") (name "/JMP") (class "Default")
      (node (ref "IR_CONTROL") (pin "23") (pinfunction "23_23") (pintype "bidirectional"))
      (node (ref "PROGRAM_COUNTER") (pin "18") (pinfunction "18_18") (pintype "bidirectional"))
    )
    (net (code "37") (name "/MARI") (class "Default")
      (node (ref "IR_CONTROL") (pin "6") (pinfunction "6_6") (pintype "bidirectional"))
      (node (ref "MAR") (pin "10") (pinfunction "10_10") (pintype "bidirectional"))
    )
    (net (code "38") (name "/MAR_HLT") (class "Default")
      (node (ref "MAR") (pin "17") (pinfunction "17_17") (pintype "bidirectional"))
      (node (ref "OR_GATE") (pin "4") (pinfunction "2A_4") (pintype "bidirectional"))
    )
    (net (code "39") (name "/MBRI") (class "Default")
      (node (ref "IR_CONTROL") (pin "2") (pinfunction "2_2") (pintype "bidirectional"))
      (node (ref "MBR") (pin "17") (pinfunction "17_17") (pintype "bidirectional"))
    )
    (net (code "40") (name "/MBRO") (class "Default")
      (node (ref "IR_CONTROL") (pin "4") (pinfunction "4_4") (pintype "bidirectional"))
      (node (ref "MBR") (pin "18") (pinfunction "18_18") (pintype "bidirectional"))
    )
    (net (code "41") (name "/MCR") (class "Default")
      (node (ref "IR_CONTROL") (pin "20") (pinfunction "20_20") (pintype "bidirectional"))
    )
    (net (code "42") (name "/OI") (class "Default")
      (node (ref "IO") (pin "18") (pinfunction "18_18") (pintype "bidirectional"))
      (node (ref "IR_CONTROL") (pin "22") (pinfunction "22_22") (pintype "bidirectional"))
    )
    (net (code "43") (name "/ONE") (class "Default")
      (node (ref "IR_CONTROL") (pin "12") (pinfunction "12_12") (pintype "bidirectional"))
    )
    (net (code "44") (name "/RI") (class "Default")
      (node (ref "IR_CONTROL") (pin "8") (pinfunction "8_8") (pintype "bidirectional"))
      (node (ref "MEMORY") (pin "18") (pinfunction "18_18") (pintype "bidirectional"))
    )
    (net (code "45") (name "/RO") (class "Default")
      (node (ref "IR_CONTROL") (pin "10") (pinfunction "10_10") (pintype "bidirectional"))
      (node (ref "MEMORY") (pin "17") (pinfunction "17_17") (pintype "bidirectional"))
    )
    (net (code "46") (name "/RST") (class "Default")
      (node (ref "FLYBACK_DIODE") (pin "C") (pinfunction "C_C") (pintype "passive"))
      (node (ref "IO") (pin "23") (pinfunction "23_23") (pintype "bidirectional"))
      (node (ref "RESET") (pin "B3") (pinfunction "N.O._2_B3") (pintype "bidirectional"))
      (node (ref "RST_RELAY") (pin "2") (pinfunction "2_2") (pintype "bidirectional"))
    )
    (net (code "47") (name "/SC") (class "Default")
      (node (ref "ACCUMULATOR") (pin "21") (pinfunction "21_21") (pintype "bidirectional"))
      (node (ref "IR_CONTROL") (pin "9") (pinfunction "9_9") (pintype "bidirectional"))
    )
    (net (code "48") (name "/SU") (class "Default")
      (node (ref "ALU") (pin "18") (pinfunction "18_18") (pintype "bidirectional"))
      (node (ref "IR_CONTROL") (pin "17") (pinfunction "17_17") (pintype "bidirectional"))
    )
    (net (code "49") (name "/SWITCHVCC") (class "Default")
      (node (ref "ACCUMULATOR") (pin "19") (pinfunction "19_19") (pintype "bidirectional"))
      (node (ref "IR") (pin "19") (pinfunction "19_19") (pintype "bidirectional"))
      (node (ref "MAR") (pin "12") (pinfunction "12_12") (pintype "bidirectional"))
      (node (ref "MBR") (pin "19") (pinfunction "19_19") (pintype "bidirectional"))
      (node (ref "RST_RELAY") (pin "1") (pinfunction "1_1") (pintype "bidirectional"))
    )
    (net (code "50") (name "/VCC") (class "Default")
      (node (ref "ALU") (pin "19") (pinfunction "19_19") (pintype "bidirectional"))
      (node (ref "CLOCK") (pin "1") (pinfunction "1_1") (pintype "bidirectional"))
      (node (ref "IO") (pin "19") (pinfunction "19_19") (pintype "bidirectional"))
      (node (ref "MEMORY") (pin "19") (pinfunction "19_19") (pintype "bidirectional"))
      (node (ref "OR_GATE") (pin "14") (pinfunction "VCC_14") (pintype "bidirectional"))
      (node (ref "POWER") (pin "1") (pinfunction "1_1") (pintype "bidirectional"))
      (node (ref "PROGRAM_COUNTER") (pin "19") (pinfunction "19_19") (pintype "bidirectional"))
      (node (ref "RESET") (pin "A1") (pinfunction "N.C._1_A1") (pintype "bidirectional"))
      (node (ref "RESET") (pin "B2") (pinfunction "COM_2_B2") (pintype "bidirectional"))
      (node (ref "RST_RELAY") (pin "5") (pinfunction "5_5") (pintype "bidirectional"))
    )
    (net (code "51") (name "/~{CLK}") (class "Default")
      (node (ref "CLOCK") (pin "4") (pinfunction "4_4") (pintype "bidirectional"))
      (node (ref "IR") (pin "17") (pinfunction "17_17") (pintype "bidirectional"))
    )
    (net (code "52") (name "/~{RST}") (class "Default")
      (node (ref "PROGRAM_COUNTER") (pin "22") (pinfunction "22_22") (pintype "bidirectional"))
      (node (ref "RESET") (pin "A2") (pinfunction "COM_1_A2") (pintype "bidirectional"))
    )
    (net (code "53") (name "Net-(LED0-PadA)") (class "Default")
      (node (ref "LED0") (pin "A") (pinfunction "A_A") (pintype "passive"))
      (node (ref "R0") (pin "1") (pinfunction "1_1") (pintype "passive"))
    )
    (net (code "54") (name "Net-(LED1-PadA)") (class "Default")
      (node (ref "LED1") (pin "A") (pinfunction "A_A") (pintype "passive"))
      (node (ref "R1") (pin "1") (pinfunction "1_1") (pintype "passive"))
    )
    (net (code "55") (name "Net-(LED2-PadA)") (class "Default")
      (node (ref "LED2") (pin "A") (pinfunction "A_A") (pintype "passive"))
      (node (ref "R2") (pin "1") (pinfunction "1_1") (pintype "passive"))
    )
    (net (code "56") (name "Net-(LED3-PadA)") (class "Default")
      (node (ref "LED3") (pin "A") (pinfunction "A_A") (pintype "passive"))
      (node (ref "R3") (pin "1") (pinfunction "1_1") (pintype "passive"))
    )
    (net (code "57") (name "Net-(LED4-PadA)") (class "Default")
      (node (ref "LED4") (pin "A") (pinfunction "A_A") (pintype "passive"))
      (node (ref "R4") (pin "1") (pinfunction "1_1") (pintype "passive"))
    )
    (net (code "58") (name "Net-(LED5-PadA)") (class "Default")
      (node (ref "LED5") (pin "A") (pinfunction "A_A") (pintype "passive"))
      (node (ref "R5") (pin "1") (pinfunction "1_1") (pintype "passive"))
    )
    (net (code "59") (name "Net-(LED6-PadA)") (class "Default")
      (node (ref "LED6") (pin "A") (pinfunction "A_A") (pintype "passive"))
      (node (ref "R6") (pin "1") (pinfunction "1_1") (pintype "passive"))
    )
    (net (code "60") (name "Net-(LED7-PadA)") (class "Default")
      (node (ref "LED7") (pin "A") (pinfunction "A_A") (pintype "passive"))
      (node (ref "R7") (pin "1") (pinfunction "1_1") (pintype "passive"))
    )
    (net (code "61") (name "Net-(LED8-PadA)") (class "Default")
      (node (ref "LED8") (pin "A") (pinfunction "A_A") (pintype "passive"))
      (node (ref "R8") (pin "1") (pinfunction "1_1") (pintype "passive"))
    )
    (net (code "62") (name "Net-(LED9-PadA)") (class "Default")
      (node (ref "LED9") (pin "A") (pinfunction "A_A") (pintype "passive"))
      (node (ref "R9") (pin "1") (pinfunction "1_1") (pintype "passive"))
    )
    (net (code "63") (name "Net-(LED10-PadA)") (class "Default")
      (node (ref "LED10") (pin "A") (pinfunction "A_A") (pintype "passive"))
      (node (ref "R10") (pin "1") (pinfunction "1_1") (pintype "passive"))
    )
    (net (code "64") (name "Net-(LED11-PadA)") (class "Default")
      (node (ref "LED11") (pin "A") (pinfunction "A_A") (pintype "passive"))
      (node (ref "R11") (pin "1") (pinfunction "1_1") (pintype "passive"))
    )
    (net (code "65") (name "Net-(LED12-PadA)") (class "Default")
      (node (ref "LED12") (pin "A") (pinfunction "A_A") (pintype "passive"))
      (node (ref "R12") (pin "1") (pinfunction "1_1") (pintype "passive"))
    )
    (net (code "66") (name "Net-(LED13-PadA)") (class "Default")
      (node (ref "LED13") (pin "A") (pinfunction "A_A") (pintype "passive"))
      (node (ref "R13") (pin "1") (pinfunction "1_1") (pintype "passive"))
    )
    (net (code "67") (name "Net-(LED14-PadA)") (class "Default")
      (node (ref "LED14") (pin "A") (pinfunction "A_A") (pintype "passive"))
      (node (ref "R14") (pin "1") (pinfunction "1_1") (pintype "passive"))
    )
    (net (code "68") (name "Net-(LED15-PadA)") (class "Default")
      (node (ref "LED15") (pin "A") (pinfunction "A_A") (pintype "passive"))
      (node (ref "R15") (pin "1") (pinfunction "1_1") (pintype "passive"))
    )
    (net (code "69") (name "Net-(OR_GATE-2Y)") (class "Default")
      (node (ref "OR_GATE") (pin "6") (pinfunction "2Y_6") (pintype "bidirectional"))
      (node (ref "OR_GATE") (pin "9") (pinfunction "3A_9") (pintype "bidirectional"))
    )
    (net (code "70") (name "unconnected-(ACCUMULATOR-Pad24)") (class "Default")
      (node (ref "ACCUMULATOR") (pin "24") (pinfunction "24_24") (pintype "bidirectional"))
    )
    (net (code "71") (name "unconnected-(CLOCK-Pad6)") (class "Default")
      (node (ref "CLOCK") (pin "6") (pinfunction "6_6") (pintype "bidirectional"))
    )
    (net (code "72") (name "unconnected-(CLOCK-Pad7)") (class "Default")
      (node (ref "CLOCK") (pin "7") (pinfunction "7_7") (pintype "bidirectional"))
    )
    (net (code "73") (name "unconnected-(CLOCK-Pad8)") (class "Default")
      (node (ref "CLOCK") (pin "8") (pinfunction "8_8") (pintype "bidirectional"))
    )
    (net (code "74") (name "unconnected-(IO-Pad24)") (class "Default")
      (node (ref "IO") (pin "24") (pinfunction "24_24") (pintype "bidirectional"))
    )
    (net (code "75") (name "unconnected-(MAR-Pad18)") (class "Default")
      (node (ref "MAR") (pin "18") (pinfunction "18_18") (pintype "bidirectional"))
    )
    (net (code "76") (name "unconnected-(MBR-Pad22)") (class "Default")
      (node (ref "MBR") (pin "22") (pinfunction "22_22") (pintype "bidirectional"))
    )
    (net (code "77") (name "unconnected-(MBR-Pad23)") (class "Default")
      (node (ref "MBR") (pin "23") (pinfunction "23_23") (pintype "bidirectional"))
    )
    (net (code "78") (name "unconnected-(MBR-Pad24)") (class "Default")
      (node (ref "MBR") (pin "24") (pinfunction "24_24") (pintype "bidirectional"))
    )
    (net (code "79") (name "unconnected-(MEMORY-Pad22)") (class "Default")
      (node (ref "MEMORY") (pin "22") (pinfunction "22_22") (pintype "bidirectional"))
    )
    (net (code "80") (name "unconnected-(MEMORY-Pad23)") (class "Default")
      (node (ref "MEMORY") (pin "23") (pinfunction "23_23") (pintype "bidirectional"))
    )
    (net (code "81") (name "unconnected-(MEMORY-Pad24)") (class "Default")
      (node (ref "MEMORY") (pin "24") (pinfunction "24_24") (pintype "bidirectional"))
    )
    (net (code "82") (name "unconnected-(OR_GATE-4Y-Pad11)") (class "Default")
      (node (ref "OR_GATE") (pin "11") (pinfunction "4Y_11") (pintype "bidirectional"))
    )
    (net (code "83") (name "unconnected-(PROGRAM_COUNTER-Pad24)") (class "Default")
      (node (ref "PROGRAM_COUNTER") (pin "24") (pinfunction "24_24") (pintype "bidirectional"))
    )
    (net (code "84") (name "unconnected-(RESET-N.C._2-PadB1)") (class "Default")
      (node (ref "RESET") (pin "B1") (pinfunction "N.C._2_B1") (pintype "bidirectional"))
    )
    (net (code "85") (name "unconnected-(RST_RELAY-Pad4)") (class "Default")
      (node (ref "RST_RELAY") (pin "4") (pinfunction "4_4") (pintype "bidirectional"))
    )
  )
)
